# esp8266S_2A_noGND.net
KiCad netlist of a schematic drawn in EAGLE
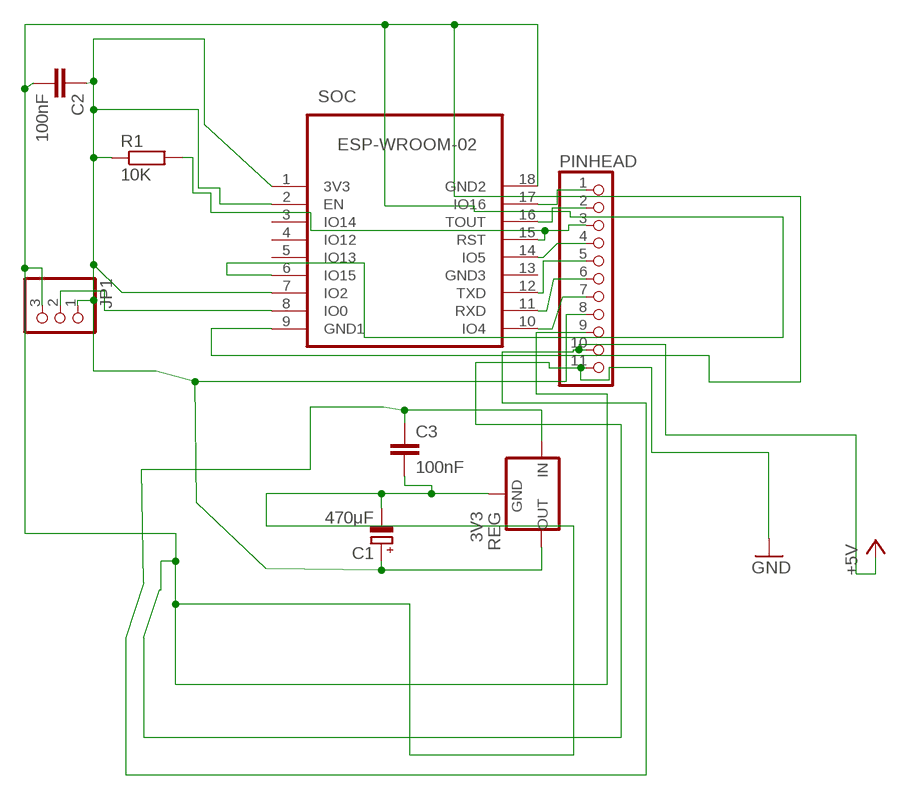
[diagram p0: schematic, sheet 1]

(export (version "E")
  (design (tool "Eeschema 10.0.6"))
  (components
    (comp (ref "C1")
      (value "470μF")
      (footprint "eagle-import:E2,5-7")
      (libsource (lib "eagle-import") (part "CPOL-EUE2.5-7"))
    )
    (comp (ref "C2")
      (value "100nF")
      (footprint "eagle-import:C0603")
      (libsource (lib "eagle-import") (part "C-EUC0603"))
    )
    (comp (ref "C3")
      (value "100nF")
      (footprint "eagle-import:C0603")
      (libsource (lib "eagle-import") (part "C-EUC0603"))
    )
    (comp (ref "JP1")
      (value "PINHD-1X3")
      (footprint "eagle-import:1X03")
      (libsource (lib "eagle-import") (part "PINHD-1X3"))
    )
    (comp (ref "PINHEAD")
      (value "PINHD-1X11")
      (footprint "eagle-import:1X11")
      (libsource (lib "eagle-import") (part "PINHD-1X11"))
    )
    (comp (ref "R1")
      (value "10K")
      (footprint "eagle-import:R0603")
      (libsource (lib "eagle-import") (part "R-EU_R0603"))
    )
    (comp (ref "REG")
      (value "3V3")
      (footprint "eagle-import:78XXS")
      (libsource (lib "eagle-import") (part "78XXS"))
    )
    (comp (ref "SOC")
      (value "ESP-WROOM-02")
      (footprint "eagle-import:FRONT-FACE-CP2")
      (libsource (lib "eagle-import") (part "ESP-WROOM-02-CP2FRONT"))
    )
  )
  (nets
    (net (code "1") (name "+5V") (class "Default")
      (node (ref "C3") (pin "1") (pinfunction "1_1") (pintype "passive"))
      (node (ref "PINHEAD") (pin "10") (pinfunction "10_10") (pintype "passive"))
      (node (ref "REG") (pin "IN") (pinfunction "IN_IN") (pintype "input"))
    )
    (net (code "2") (name "GND") (class "Default")
      (node (ref "C1") (pin "-") (pinfunction "-_-") (pintype "passive"))
      (node (ref "C2") (pin "2") (pinfunction "2_2") (pintype "passive"))
      (node (ref "C3") (pin "2") (pinfunction "2_2") (pintype "passive"))
      (node (ref "JP1") (pin "3") (pinfunction "3_3") (pintype "passive"))
      (node (ref "PINHEAD") (pin "11") (pinfunction "11_11") (pintype "passive"))
      (node (ref "PINHEAD") (pin "9") (pinfunction "9_9") (pintype "passive"))
      (node (ref "REG") (pin "GND") (pinfunction "GND_GND") (pintype "input"))
      (node (ref "SOC") (pin "18") (pinfunction "GND2_18") (pintype "bidirectional"))
      (node (ref "SOC") (pin "6") (pinfunction "IO15_6") (pintype "bidirectional"))
      (node (ref "SOC") (pin "9") (pinfunction "GND1_9") (pintype "bidirectional"))
    )
    (net (code "3") (name "Net-(SOC-3V3)") (class "Default")
      (node (ref "C1") (pin "+") (pinfunction "+_+") (pintype "passive"))
      (node (ref "C2") (pin "1") (pinfunction "1_1") (pintype "passive"))
      (node (ref "JP1") (pin "1") (pinfunction "1_1") (pintype "passive"))
      (node (ref "PINHEAD") (pin "8") (pinfunction "8_8") (pintype "passive"))
      (node (ref "R1") (pin "1") (pinfunction "1_1") (pintype "passive"))
      (node (ref "REG") (pin "OUT") (pinfunction "OUT_OUT") (pintype "passive"))
      (node (ref "SOC") (pin "1") (pinfunction "3V3_1") (pintype "bidirectional"))
      (node (ref "SOC") (pin "2") (pinfunction "EN_2") (pintype "bidirectional"))
      (node (ref "SOC") (pin "7") (pinfunction "IO2_7") (pintype "bidirectional"))
    )
    (net (code "4") (name "Net-(SOC-IO0)") (class "Default")
      (node (ref "JP1") (pin "2") (pinfunction "2_2") (pintype "passive"))
      (node (ref "SOC") (pin "8") (pinfunction "IO0_8") (pintype "bidirectional"))
    )
    (net (code "5") (name "Net-(SOC-IO4)") (class "Default")
      (node (ref "PINHEAD") (pin "7") (pinfunction "7_7") (pintype "passive"))
      (node (ref "SOC") (pin "10") (pinfunction "IO4_10") (pintype "bidirectional"))
    )
    (net (code "6") (name "Net-(SOC-IO5)") (class "Default")
      (node (ref "PINHEAD") (pin "4") (pinfunction "4_4") (pintype "passive"))
      (node (ref "SOC") (pin "14") (pinfunction "IO5_14") (pintype "bidirectional"))
    )
    (net (code "7") (name "Net-(SOC-IO16)") (class "Default")
      (node (ref "PINHEAD") (pin "1") (pinfunction "1_1") (pintype "passive"))
      (node (ref "SOC") (pin "17") (pinfunction "IO16_17") (pintype "bidirectional"))
    )
    (net (code "8") (name "Net-(SOC-RST)") (class "Default")
      (node (ref "PINHEAD") (pin "3") (pinfunction "3_3") (pintype "passive"))
      (node (ref "R1") (pin "2") (pinfunction "2_2") (pintype "passive"))
      (node (ref "SOC") (pin "15") (pinfunction "RST_15") (pintype "bidirectional"))
    )
    (net (code "9") (name "Net-(SOC-RXD)") (class "Default")
      (node (ref "PINHEAD") (pin "6") (pinfunction "6_6") (pintype "passive"))
      (node (ref "SOC") (pin "11") (pinfunction "RXD_11") (pintype "bidirectional"))
    )
    (net (code "10") (name "Net-(SOC-TOUT)") (class "Default")
      (node (ref "PINHEAD") (pin "2") (pinfunction "2_2") (pintype "passive"))
      (node (ref "SOC") (pin "16") (pinfunction "TOUT_16") (pintype "bidirectional"))
    )
    (net (code "11") (name "Net-(SOC-TXD)") (class "Default")
      (node (ref "PINHEAD") (pin "5") (pinfunction "5_5") (pintype "passive"))
      (node (ref "SOC") (pin "12") (pinfunction "TXD_12") (pintype "bidirectional"))
    )
    (net (code "12") (name "unconnected-(SOC-GND3-Pad13)") (class "Default")
      (node (ref "SOC") (pin "13") (pinfunction "GND3_13") (pintype "bidirectional"))
    )
    (net (code "13") (name "unconnected-(SOC-IO12-Pad4)") (class "Default")
      (node (ref "SOC") (pin "4") (pinfunction "IO12_4") (pintype "bidirectional"))
    )
    (net (code "14") (name "unconnected-(SOC-IO13-Pad5)") (class "Default")
      (node (ref "SOC") (pin "5") (pinfunction "IO13_5") (pintype "open_collector"))
    )
    (net (code "15") (name "unconnected-(SOC-IO14-Pad3)") (class "Default")
      (node (ref "SOC") (pin "3") (pinfunction "IO14_3") (pintype "bidirectional"))
    )
  )
)
